# Boost.net
KiCad netlist of a schematic drawn in Altium Designer
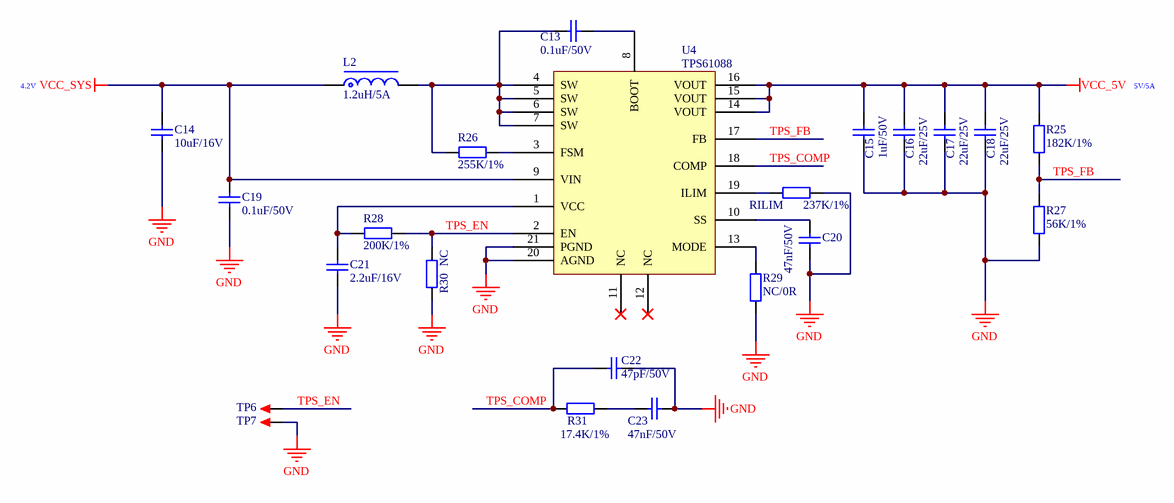
[diagram p0: Boost.SchDoc]

(export (version "E")
  (design (tool "Eeschema 10.0.6"))
  (components
    (comp (ref "C13")
      (value "0.1uF/50V")
      (footprint "C0402_L")
      (description "贴片电容")
      (libsource (lib "0.1 - 电阻-电容-电感-晶振-晶体-磁珠-电位器") (part "C"))
    )
    (comp (ref "C14")
      (value "10uF/16V")
      (footprint "C0805_L")
      (description "贴片电容")
      (libsource (lib "0.1 - 电阻-电容-电感-晶振-晶体-磁珠-电位器") (part "C"))
    )
    (comp (ref "C15")
      (value "1uF/50V")
      (footprint "C0603_L")
      (description "贴片电容")
      (libsource (lib "0.1 - 电阻-电容-电感-晶振-晶体-磁珠-电位器") (part "C"))
    )
    (comp (ref "C16")
      (value "22uF/25V")
      (footprint "C1206_L")
      (description "贴片电容")
      (libsource (lib "0.1 - 电阻-电容-电感-晶振-晶体-磁珠-电位器") (part "C"))
    )
    (comp (ref "C17")
      (value "22uF/25V")
      (footprint "C1206_L")
      (description "贴片电容")
      (libsource (lib "0.1 - 电阻-电容-电感-晶振-晶体-磁珠-电位器") (part "C"))
    )
    (comp (ref "C18")
      (value "22uF/25V")
      (footprint "C1206_L")
      (description "贴片电容")
      (libsource (lib "0.1 - 电阻-电容-电感-晶振-晶体-磁珠-电位器") (part "C"))
    )
    (comp (ref "C19")
      (value "0.1uF/50V")
      (footprint "C0402_L")
      (description "贴片电容")
      (libsource (lib "0.1 - 电阻-电容-电感-晶振-晶体-磁珠-电位器") (part "C"))
    )
    (comp (ref "C20")
      (value "47nF/50V")
      (footprint "C0402_L")
      (description "贴片电容")
      (libsource (lib "0.1 - 电阻-电容-电感-晶振-晶体-磁珠-电位器") (part "C"))
    )
    (comp (ref "C21")
      (value "2.2uF/16V")
      (footprint "C0603_L")
      (description "贴片电容")
      (libsource (lib "0.1 - 电阻-电容-电感-晶振-晶体-磁珠-电位器") (part "C"))
    )
    (comp (ref "C22")
      (value "47pF/50V")
      (footprint "C0402_L")
      (description "贴片电容")
      (libsource (lib "0.1 - 电阻-电容-电感-晶振-晶体-磁珠-电位器") (part "C"))
    )
    (comp (ref "C23")
      (value "47nF/50V")
      (footprint "C0402_L")
      (description "贴片电容")
      (libsource (lib "0.1 - 电阻-电容-电感-晶振-晶体-磁珠-电位器") (part "C"))
    )
    (comp (ref "L2")
      (value "1.2uH/5A")
      (footprint "L-SMD-0630")
      (description "功率电感")
      (libsource (lib "0.1 - 电阻-电容-电感-晶振-晶体-磁珠-电位器") (part "L-CDRH"))
    )
    (comp (ref "R25")
      (value "182K/1%")
      (footprint "R0402_L")
      (description "贴片电阻")
      (libsource (lib "0.1 - 电阻-电容-电感-晶振-晶体-磁珠-电位器") (part "R"))
    )
    (comp (ref "R26")
      (value "255K/1%")
      (footprint "R0402_L")
      (description "贴片电阻")
      (libsource (lib "0.1 - 电阻-电容-电感-晶振-晶体-磁珠-电位器") (part "R"))
    )
    (comp (ref "R27")
      (value "56K/1%")
      (footprint "R0402_L")
      (description "贴片电阻")
      (libsource (lib "0.1 - 电阻-电容-电感-晶振-晶体-磁珠-电位器") (part "R"))
    )
    (comp (ref "R28")
      (value "200K/1%")
      (footprint "R0402_L")
      (description "贴片电阻")
      (libsource (lib "0.1 - 电阻-电容-电感-晶振-晶体-磁珠-电位器") (part "R"))
    )
    (comp (ref "R29")
      (value "NC/0R")
      (footprint "R0402_L")
      (description "贴片电阻")
      (libsource (lib "0.1 - 电阻-电容-电感-晶振-晶体-磁珠-电位器") (part "R"))
    )
    (comp (ref "R30")
      (value "NC")
      (footprint "R0402_L")
      (description "贴片电阻")
      (libsource (lib "0.1 - 电阻-电容-电感-晶振-晶体-磁珠-电位器") (part "R"))
    )
    (comp (ref "R31")
      (value "17.4K/1%")
      (footprint "R0402_L")
      (description "贴片电阻")
      (libsource (lib "0.1 - 电阻-电容-电感-晶振-晶体-磁珠-电位器") (part "R"))
    )
    (comp (ref "RILIM")
      (value "237K/1%")
      (footprint "R0402_L")
      (description "贴片电阻")
      (libsource (lib "0.1 - 电阻-电容-电感-晶振-晶体-磁珠-电位器") (part "R"))
    )
    (comp (ref "TP6")
      (value "TEST")
      (footprint "TEST 1")
      (description "测试点")
      (libsource (lib "0.5 - 按键-开关-蜂鸣器-保险丝-电池-测试点-Mark点") (part "TEST"))
    )
    (comp (ref "TP7")
      (value "TEST")
      (footprint "TEST 1")
      (description "测试点")
      (libsource (lib "0.5 - 按键-开关-蜂鸣器-保险丝-电池-测试点-Mark点") (part "TEST"))
    )
    (comp (ref "U4")
      (value "TPS61088")
      (footprint "VQFN-20")
      (description "10A 全集成同步升压转换器")
      (libsource (lib "lib") (part "TPS61088"))
    )
  )
  (nets
    (net (code "1") (name "/TPS_COMP") (class "Default")
      (node (ref "C22") (pin "1") (pinfunction "1_1") (pintype "passive"))
      (node (ref "R31") (pin "1") (pinfunction "1_1") (pintype "passive"))
      (node (ref "U4") (pin "18") (pinfunction "COMP_18") (pintype "passive"))
    )
    (net (code "2") (name "/TPS_EN") (class "Default")
      (node (ref "R28") (pin "2") (pinfunction "2_2") (pintype "passive"))
      (node (ref "R30") (pin "2") (pinfunction "2_2") (pintype "passive"))
      (node (ref "TP6") (pin "1") (pinfunction "1_1") (pintype "passive"))
      (node (ref "U4") (pin "2") (pinfunction "EN_2") (pintype "passive"))
    )
    (net (code "3") (name "/TPS_FB") (class "Default")
      (node (ref "R25") (pin "1") (pinfunction "1_1") (pintype "passive"))
      (node (ref "R27") (pin "2") (pinfunction "2_2") (pintype "passive"))
      (node (ref "U4") (pin "17") (pinfunction "FB_17") (pintype "passive"))
    )
    (net (code "4") (name "GND") (class "Default")
      (node (ref "C14") (pin "1") (pinfunction "1_1") (pintype "passive"))
      (node (ref "C15") (pin "1") (pinfunction "1_1") (pintype "passive"))
      (node (ref "C16") (pin "1") (pinfunction "1_1") (pintype "passive"))
      (node (ref "C17") (pin "1") (pinfunction "1_1") (pintype "passive"))
      (node (ref "C18") (pin "1") (pinfunction "1_1") (pintype "passive"))
      (node (ref "C19") (pin "1") (pinfunction "1_1") (pintype "passive"))
      (node (ref "C20") (pin "1") (pinfunction "1_1") (pintype "passive"))
      (node (ref "C21") (pin "1") (pinfunction "1_1") (pintype "passive"))
      (node (ref "C22") (pin "2") (pinfunction "2_2") (pintype "passive"))
      (node (ref "C23") (pin "2") (pinfunction "2_2") (pintype "passive"))
      (node (ref "R27") (pin "1") (pinfunction "1_1") (pintype "passive"))
      (node (ref "R29") (pin "1") (pinfunction "1_1") (pintype "passive"))
      (node (ref "R30") (pin "1") (pinfunction "1_1") (pintype "passive"))
      (node (ref "RILIM") (pin "2") (pinfunction "2_2") (pintype "passive"))
      (node (ref "TP7") (pin "1") (pinfunction "1_1") (pintype "passive"))
      (node (ref "U4") (pin "20") (pinfunction "AGND_20") (pintype "passive"))
      (node (ref "U4") (pin "21") (pinfunction "PGND_21") (pintype "passive"))
    )
    (net (code "5") (name "Net-(C13-Pad1)") (class "Default")
      (node (ref "C13") (pin "1") (pinfunction "1_1") (pintype "passive"))
      (node (ref "L2") (pin "2") (pinfunction "2_2") (pintype "passive"))
      (node (ref "R26") (pin "1") (pinfunction "1_1") (pintype "passive"))
      (node (ref "U4") (pin "4") (pinfunction "SW_4") (pintype "passive"))
      (node (ref "U4") (pin "5") (pinfunction "SW_5") (pintype "passive"))
      (node (ref "U4") (pin "6") (pinfunction "SW_6") (pintype "passive"))
      (node (ref "U4") (pin "7") (pinfunction "SW_7") (pintype "passive"))
    )
    (net (code "6") (name "Net-(C23-Pad1)") (class "Default")
      (node (ref "C23") (pin "1") (pinfunction "1_1") (pintype "passive"))
      (node (ref "R31") (pin "2") (pinfunction "2_2") (pintype "passive"))
    )
    (net (code "7") (name "Net-(U4-BOOT)") (class "Default")
      (node (ref "C13") (pin "2") (pinfunction "2_2") (pintype "passive"))
      (node (ref "U4") (pin "8") (pinfunction "BOOT_8") (pintype "passive"))
    )
    (net (code "8") (name "Net-(U4-FSM)") (class "Default")
      (node (ref "R26") (pin "2") (pinfunction "2_2") (pintype "passive"))
      (node (ref "U4") (pin "3") (pinfunction "FSM_3") (pintype "passive"))
    )
    (net (code "9") (name "Net-(U4-ILIM)") (class "Default")
      (node (ref "RILIM") (pin "1") (pinfunction "1_1") (pintype "passive"))
      (node (ref "U4") (pin "19") (pinfunction "ILIM_19") (pintype "passive"))
    )
    (net (code "10") (name "Net-(U4-MODE)") (class "Default")
      (node (ref "R29") (pin "2") (pinfunction "2_2") (pintype "passive"))
      (node (ref "U4") (pin "13") (pinfunction "MODE_13") (pintype "passive"))
    )
    (net (code "11") (name "Net-(U4-SS)") (class "Default")
      (node (ref "C20") (pin "2") (pinfunction "2_2") (pintype "passive"))
      (node (ref "U4") (pin "10") (pinfunction "SS_10") (pintype "passive"))
    )
    (net (code "12") (name "Net-(U4-VCC)") (class "Default")
      (node (ref "C21") (pin "2") (pinfunction "2_2") (pintype "passive"))
      (node (ref "R28") (pin "1") (pinfunction "1_1") (pintype "passive"))
      (node (ref "U4") (pin "1") (pinfunction "VCC_1") (pintype "passive"))
    )
    (net (code "13") (name "VCC_5V") (class "Default")
      (node (ref "C15") (pin "2") (pinfunction "2_2") (pintype "passive"))
      (node (ref "C16") (pin "2") (pinfunction "2_2") (pintype "passive"))
      (node (ref "C17") (pin "2") (pinfunction "2_2") (pintype "passive"))
      (node (ref "C18") (pin "2") (pinfunction "2_2") (pintype "passive"))
      (node (ref "R25") (pin "2") (pinfunction "2_2") (pintype "passive"))
      (node (ref "U4") (pin "14") (pinfunction "VOUT_14") (pintype "passive"))
      (node (ref "U4") (pin "15") (pinfunction "VOUT_15") (pintype "passive"))
      (node (ref "U4") (pin "16") (pinfunction "VOUT_16") (pintype "passive"))
    )
    (net (code "14") (name "VCC_SYS") (class "Default")
      (node (ref "C14") (pin "2") (pinfunction "2_2") (pintype "passive"))
      (node (ref "C19") (pin "2") (pinfunction "2_2") (pintype "passive"))
      (node (ref "L2") (pin "1") (pinfunction "1_1") (pintype "passive"))
      (node (ref "U4") (pin "9") (pinfunction "VIN_9") (pintype "passive"))
    )
    (net (code "15") (name "unconnected-(U4-NC-Pad11)") (class "Default")
      (node (ref "U4") (pin "11") (pinfunction "NC_11") (pintype "passive+no_connect"))
    )
    (net (code "16") (name "unconnected-(U4-NC-Pad12)") (class "Default")
      (node (ref "U4") (pin "12") (pinfunction "NC_12") (pintype "passive+no_connect"))
    )
  )
)
